# logger_thruhole_2.net
KiCad netlist of a schematic drawn in EAGLE
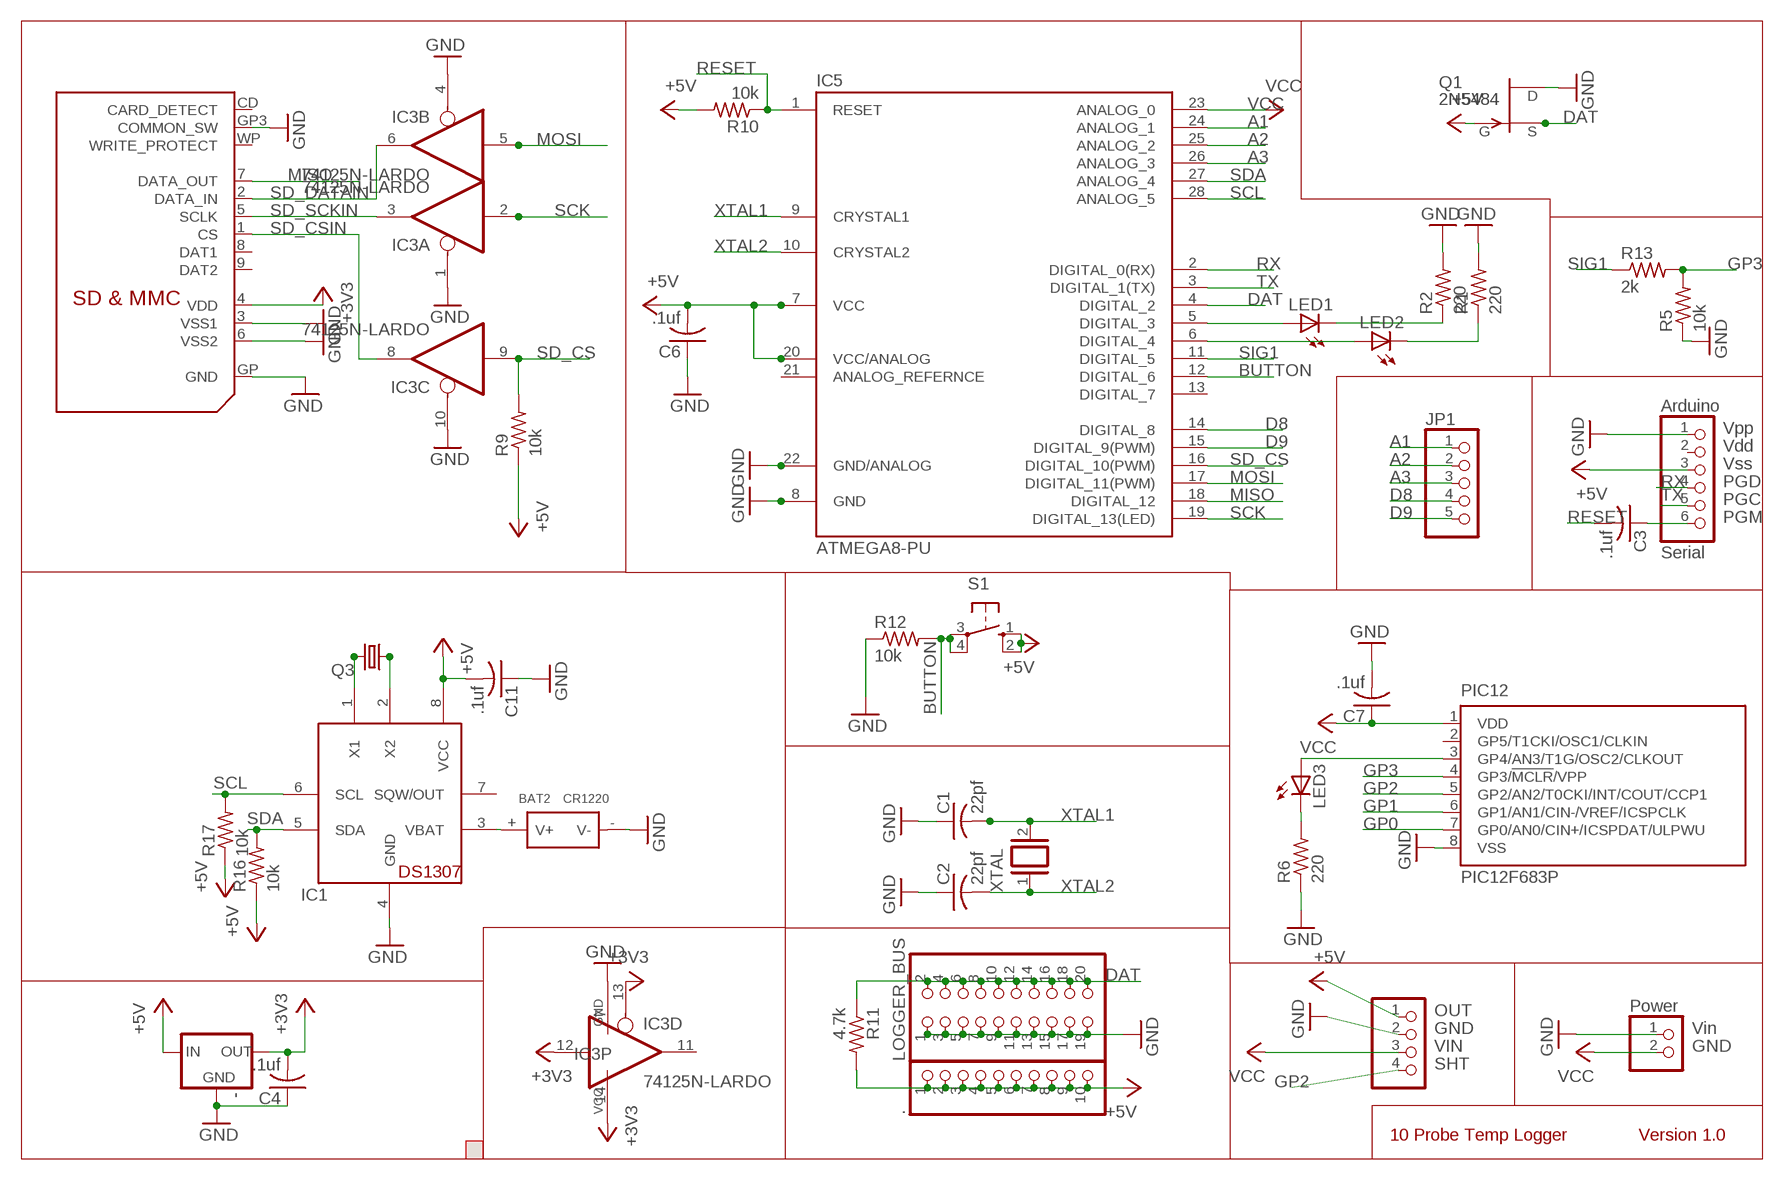
[diagram p0: schematic, sheet 1]

(export (version "E")
  (design (tool "Eeschema 10.0.6"))
  (components
    (comp (ref "'")
      (value "MCP1700TRI")
      (footprint "eagle-import:TO92")
      (libsource (lib "eagle-import") (part "MCP1700TRI"))
    )
    (comp (ref ".")
      (value "PINHD-1X10")
      (footprint "eagle-import:1X10")
      (libsource (lib "eagle-import") (part "PINHD-1X10"))
    )
    (comp (ref "BAT2")
      (value "CR1220")
      (footprint "eagle-import:BAT2P-SMD-16.4-CR1220")
      (libsource (lib "eagle-import") (part "SMD-BATTERY-CELL-HOLDER-PLASTIC"))
    )
    (comp (ref "C1")
      (value "22pf")
      (footprint "eagle-import:C025-025X050")
      (libsource (lib "eagle-import") (part "C-US025-025X050"))
    )
    (comp (ref "C2")
      (value "22pf")
      (footprint "eagle-import:C025-025X050")
      (libsource (lib "eagle-import") (part "C-US025-025X050"))
    )
    (comp (ref "C3")
      (value ".1uf")
      (footprint "eagle-import:C025-025X050")
      (libsource (lib "eagle-import") (part "C-US025-025X050"))
    )
    (comp (ref "C4")
      (value ".1uf")
      (footprint "eagle-import:C025-025X050")
      (libsource (lib "eagle-import") (part "C-US025-025X050"))
    )
    (comp (ref "C6")
      (value ".1uf")
      (footprint "eagle-import:C025-025X050")
      (libsource (lib "eagle-import") (part "C-US025-025X050"))
    )
    (comp (ref "C7")
      (value ".1uf")
      (footprint "eagle-import:C025-025X050")
      (libsource (lib "eagle-import") (part "C-US025-025X050"))
    )
    (comp (ref "C11")
      (value ".1uf")
      (footprint "eagle-import:C025-025X050")
      (libsource (lib "eagle-import") (part "C-US025-025X050"))
    )
    (comp (ref "IC1")
      (value "DS1307")
      (footprint "eagle-import:DIL08")
      (libsource (lib "eagle-import") (part "DS1307"))
    )
    (comp (ref "IC3")
      (value "74125N-LARDO")
      (footprint "eagle-import:DIL14-LARDO")
      (libsource (lib "eagle-import") (part "74125N-LARDO"))
    )
    (comp (ref "IC5")
      (value "ATMEGA8-PU")
      (footprint "eagle-import:DIL28-3")
      (libsource (lib "eagle-import") (part "ATMEGA8-PU"))
    )
    (comp (ref "JP1")
      (value "PINHD-1X5")
      (footprint "eagle-import:1X05")
      (libsource (lib "eagle-import") (part "PINHD-1X5"))
    )
    (comp (ref "JP2")
      (value "PINHD-1X6")
      (footprint "eagle-import:1X06")
      (libsource (lib "eagle-import") (part "PINHD-1X6"))
    )
    (comp (ref "LED1")
      (value "LEDLZR181")
      (footprint "eagle-import:LZR181")
      (libsource (lib "eagle-import") (part "LEDLZR181"))
    )
    (comp (ref "LED2")
      (value "LEDLZR181")
      (footprint "eagle-import:LZR181")
      (libsource (lib "eagle-import") (part "LEDLZR181"))
    )
    (comp (ref "LED3")
      (value "LEDLZR181")
      (footprint "eagle-import:LZR181")
      (libsource (lib "eagle-import") (part "LEDLZR181"))
    )
    (comp (ref "LOGGER_BUS")
      (value "PINHD-2X10")
      (footprint "eagle-import:2X10")
      (libsource (lib "eagle-import") (part "PINHD-2X10"))
    )
    (comp (ref "PIC12")
      (value "PIC12F683P")
      (footprint "eagle-import:DIL8")
      (fields (field (name "MF") "MICROCHIP") (field (name "MPN") "PIC12F683-I/P"))
      (libsource (lib "eagle-import") (part "PIC12F683P"))
    )
    (comp (ref "POWER")
      (value "PINHD-1X2")
      (footprint "eagle-import:1X02")
      (libsource (lib "eagle-import") (part "PINHD-1X2"))
    )
    (comp (ref "Q1")
      (value "2N5484")
      (footprint "eagle-import:TO92-")
      (libsource (lib "eagle-import") (part "?5482N4"))
    )
    (comp (ref "Q3")
      (value "CRYSTALTC38H")
      (footprint "eagle-import:TC38H")
      (libsource (lib "eagle-import") (part "CRYSTALTC38H"))
    )
    (comp (ref "R1")
      (value "220")
      (footprint "eagle-import:0207_2V")
      (libsource (lib "eagle-import") (part "R-US_0207/2V"))
    )
    (comp (ref "R2")
      (value "220")
      (footprint "eagle-import:0207_2V")
      (libsource (lib "eagle-import") (part "R-US_0207/2V"))
    )
    (comp (ref "R5")
      (value "10k")
      (footprint "eagle-import:0207_2V")
      (libsource (lib "eagle-import") (part "R-US_0207/2V"))
    )
    (comp (ref "R6")
      (value "220")
      (footprint "eagle-import:0207_2V")
      (libsource (lib "eagle-import") (part "R-US_0207/2V"))
    )
    (comp (ref "R9")
      (value "10k")
      (footprint "eagle-import:0207_2V")
      (libsource (lib "eagle-import") (part "R-US_0207/2V"))
    )
    (comp (ref "R10")
      (value "10k")
      (footprint "eagle-import:0207_2V")
      (libsource (lib "eagle-import") (part "R-US_0207/2V"))
    )
    (comp (ref "R11")
      (value "4.7k")
      (footprint "eagle-import:0207_2V")
      (libsource (lib "eagle-import") (part "R-US_0207/2V"))
    )
    (comp (ref "R12")
      (value "10k")
      (footprint "eagle-import:0207_2V")
      (libsource (lib "eagle-import") (part "R-US_0207/2V"))
    )
    (comp (ref "R13")
      (value "2k")
      (footprint "eagle-import:0207_2V")
      (libsource (lib "eagle-import") (part "R-US_0207/2V"))
    )
    (comp (ref "R16")
      (value "10k")
      (footprint "eagle-import:0207_2V")
      (libsource (lib "eagle-import") (part "R-US_0207/2V"))
    )
    (comp (ref "R17")
      (value "10k")
      (footprint "eagle-import:0207_2V")
      (libsource (lib "eagle-import") (part "R-US_0207/2V"))
    )
    (comp (ref "REG")
      (value "PINHD-1X4")
      (footprint "eagle-import:1X04")
      (libsource (lib "eagle-import") (part "PINHD-1X4"))
    )
    (comp (ref "S1")
      (value "10-XX")
      (footprint "eagle-import:B3F-10XX")
      (fields (field (name "MPN") "B3F-1000"))
      (libsource (lib "eagle-import") (part "10-XX"))
    )
    (comp (ref "U$2")
      (value "SDMMC06132")
      (footprint "eagle-import:06132")
      (libsource (lib "eagle-import") (part "SDMMC06132"))
    )
    (comp (ref "XTAL")
      (value "XTAL/S")
      (footprint "eagle-import:QS")
      (libsource (lib "eagle-import") (part "XTAL/S"))
    )
  )
  (nets
    (net (code "1") (name "+3V3") (class "Default")
      (node (ref "'") (pin "3") (pinfunction "OUT_3") (pintype "passive"))
      (node (ref "C4") (pin "2") (pinfunction "2_2") (pintype "passive"))
      (node (ref "IC3") (pin "12") (pinfunction "I_12") (pintype "input"))
      (node (ref "IC3") (pin "13") (pinfunction "OE_13") (pintype "input"))
      (node (ref "IC3") (pin "14") (pinfunction "VCC_14") (pintype "power_in"))
      (node (ref "U$2") (pin "4") (pinfunction "VDD_4") (pintype "power_in"))
    )
    (net (code "2") (name "+5V") (class "Default")
      (node (ref "'") (pin "2") (pinfunction "IN_2") (pintype "input"))
      (node (ref ".") (pin "1") (pinfunction "1_1") (pintype "passive"))
      (node (ref ".") (pin "10") (pinfunction "10_10") (pintype "passive"))
      (node (ref ".") (pin "2") (pinfunction "2_2") (pintype "passive"))
      (node (ref ".") (pin "3") (pinfunction "3_3") (pintype "passive"))
      (node (ref ".") (pin "4") (pinfunction "4_4") (pintype "passive"))
      (node (ref ".") (pin "5") (pinfunction "5_5") (pintype "passive"))
      (node (ref ".") (pin "6") (pinfunction "6_6") (pintype "passive"))
      (node (ref ".") (pin "7") (pinfunction "7_7") (pintype "passive"))
      (node (ref ".") (pin "8") (pinfunction "8_8") (pintype "passive"))
      (node (ref ".") (pin "9") (pinfunction "9_9") (pintype "passive"))
      (node (ref "C11") (pin "2") (pinfunction "2_2") (pintype "passive"))
      (node (ref "C6") (pin "2") (pinfunction "2_2") (pintype "passive"))
      (node (ref "IC1") (pin "8") (pinfunction "VCC_8") (pintype "power_in"))
      (node (ref "IC5") (pin "20") (pinfunction "VCC/ANALOG_20") (pintype "passive"))
      (node (ref "IC5") (pin "7") (pinfunction "VCC_7") (pintype "power_in"))
      (node (ref "JP2") (pin "3") (pinfunction "3_3") (pintype "passive"))
      (node (ref "Q1") (pin "1") (pinfunction "G_1") (pintype "passive"))
      (node (ref "R10") (pin "2") (pinfunction "2_2") (pintype "passive"))
      (node (ref "R11") (pin "2") (pinfunction "2_2") (pintype "passive"))
      (node (ref "R16") (pin "1") (pinfunction "1_1") (pintype "passive"))
      (node (ref "R17") (pin "1") (pinfunction "1_1") (pintype "passive"))
      (node (ref "R9") (pin "1") (pinfunction "1_1") (pintype "passive"))
      (node (ref "REG") (pin "1") (pinfunction "1_1") (pintype "passive"))
      (node (ref "S1") (pin "1") (pinfunction "S_1") (pintype "passive"))
      (node (ref "S1") (pin "2") (pinfunction "S1_2") (pintype "passive"))
    )
    (net (code "3") (name "/A1") (class "Default")
      (node (ref "IC5") (pin "24") (pinfunction "ANALOG_1_24") (pintype "bidirectional"))
      (node (ref "JP1") (pin "1") (pinfunction "1_1") (pintype "passive"))
    )
    (net (code "4") (name "/A2") (class "Default")
      (node (ref "IC5") (pin "25") (pinfunction "ANALOG_2_25") (pintype "bidirectional"))
      (node (ref "JP1") (pin "2") (pinfunction "2_2") (pintype "passive"))
    )
    (net (code "5") (name "/A3") (class "Default")
      (node (ref "IC5") (pin "26") (pinfunction "ANALOG_3_26") (pintype "bidirectional"))
      (node (ref "JP1") (pin "3") (pinfunction "3_3") (pintype "passive"))
    )
    (net (code "6") (name "/BUTTON") (class "Default")
      (node (ref "IC5") (pin "12") (pinfunction "DIGITAL_6_12") (pintype "bidirectional"))
      (node (ref "R12") (pin "2") (pinfunction "2_2") (pintype "passive"))
      (node (ref "S1") (pin "3") (pinfunction "P_3") (pintype "passive"))
      (node (ref "S1") (pin "4") (pinfunction "P1_4") (pintype "passive"))
    )
    (net (code "7") (name "/D8") (class "Default")
      (node (ref "IC5") (pin "14") (pinfunction "DIGITAL_8_14") (pintype "bidirectional"))
      (node (ref "JP1") (pin "4") (pinfunction "4_4") (pintype "passive"))
    )
    (net (code "8") (name "/D9") (class "Default")
      (node (ref "IC5") (pin "15") (pinfunction "DIGITAL_9(PWM)_15") (pintype "bidirectional"))
      (node (ref "JP1") (pin "5") (pinfunction "5_5") (pintype "passive"))
    )
    (net (code "9") (name "/DAT") (class "Default")
      (node (ref "IC5") (pin "4") (pinfunction "DIGITAL_2_4") (pintype "bidirectional"))
      (node (ref "LOGGER_BUS") (pin "10") (pinfunction "10_10") (pintype "passive"))
      (node (ref "LOGGER_BUS") (pin "12") (pinfunction "12_12") (pintype "passive"))
      (node (ref "LOGGER_BUS") (pin "14") (pinfunction "14_14") (pintype "passive"))
      (node (ref "LOGGER_BUS") (pin "16") (pinfunction "16_16") (pintype "passive"))
      (node (ref "LOGGER_BUS") (pin "18") (pinfunction "18_18") (pintype "passive"))
      (node (ref "LOGGER_BUS") (pin "2") (pinfunction "2_2") (pintype "passive"))
      (node (ref "LOGGER_BUS") (pin "20") (pinfunction "20_20") (pintype "passive"))
      (node (ref "LOGGER_BUS") (pin "4") (pinfunction "4_4") (pintype "passive"))
      (node (ref "LOGGER_BUS") (pin "6") (pinfunction "6_6") (pintype "passive"))
      (node (ref "LOGGER_BUS") (pin "8") (pinfunction "8_8") (pintype "passive"))
      (node (ref "Q1") (pin "2") (pinfunction "S_2") (pintype "passive"))
      (node (ref "R11") (pin "1") (pinfunction "1_1") (pintype "passive"))
    )
    (net (code "10") (name "/GP0") (class "Default")
      (node (ref "PIC12") (pin "7") (pinfunction "GP0/AN0/CIN+/ICSPDAT/ULPWU_7") (pintype "bidirectional"))
    )
    (net (code "11") (name "/GP1") (class "Default")
      (node (ref "PIC12") (pin "6") (pinfunction "GP1/AN1/CIN-/VREF/ICSPCLK_6") (pintype "bidirectional"))
    )
    (net (code "12") (name "/GP2") (class "Default")
      (node (ref "PIC12") (pin "5") (pinfunction "GP2/AN2/T0CKI/INT/COUT/CCP1_5") (pintype "bidirectional"))
      (node (ref "REG") (pin "4") (pinfunction "4_4") (pintype "passive"))
    )
    (net (code "13") (name "/GP3") (class "Default")
      (node (ref "PIC12") (pin "4") (pinfunction "GP3/~{MCLR}/VPP_4") (pintype "bidirectional"))
      (node (ref "R13") (pin "2") (pinfunction "2_2") (pintype "passive"))
      (node (ref "R5") (pin "2") (pinfunction "2_2") (pintype "passive"))
    )
    (net (code "14") (name "/MISO") (class "Default")
      (node (ref "IC5") (pin "18") (pinfunction "DIGITAL_12_18") (pintype "bidirectional"))
      (node (ref "U$2") (pin "7") (pinfunction "DATA_OUT_7") (pintype "output"))
    )
    (net (code "15") (name "/MOSI") (class "Default")
      (node (ref "IC3") (pin "5") (pinfunction "I_5") (pintype "input"))
      (node (ref "IC5") (pin "17") (pinfunction "DIGITAL_11(PWM)_17") (pintype "bidirectional"))
    )
    (net (code "16") (name "/RESET") (class "Default")
      (node (ref "C3") (pin "2") (pinfunction "2_2") (pintype "passive"))
      (node (ref "IC5") (pin "1") (pinfunction "RESET_1") (pintype "bidirectional"))
      (node (ref "R10") (pin "1") (pinfunction "1_1") (pintype "passive"))
    )
    (net (code "17") (name "/RX") (class "Default")
      (node (ref "IC5") (pin "2") (pinfunction "DIGITAL_0(RX)_2") (pintype "bidirectional"))
      (node (ref "JP2") (pin "4") (pinfunction "4_4") (pintype "passive"))
    )
    (net (code "18") (name "/SCK") (class "Default")
      (node (ref "IC3") (pin "2") (pinfunction "I_2") (pintype "input"))
      (node (ref "IC5") (pin "19") (pinfunction "DIGITAL_13(LED)_19") (pintype "bidirectional"))
    )
    (net (code "19") (name "/SCL") (class "Default")
      (node (ref "IC1") (pin "6") (pinfunction "SCL_6") (pintype "bidirectional"))
      (node (ref "IC5") (pin "28") (pinfunction "ANALOG_5_28") (pintype "bidirectional"))
      (node (ref "R17") (pin "2") (pinfunction "2_2") (pintype "passive"))
    )
    (net (code "20") (name "/SDA") (class "Default")
      (node (ref "IC1") (pin "5") (pinfunction "SDA_5") (pintype "bidirectional"))
      (node (ref "IC5") (pin "27") (pinfunction "ANALOG_4_27") (pintype "bidirectional"))
      (node (ref "R16") (pin "2") (pinfunction "2_2") (pintype "passive"))
    )
    (net (code "21") (name "/SD_CS") (class "Default")
      (node (ref "IC3") (pin "9") (pinfunction "I_9") (pintype "input"))
      (node (ref "IC5") (pin "16") (pinfunction "DIGITAL_10(PWM)_16") (pintype "bidirectional"))
      (node (ref "R9") (pin "2") (pinfunction "2_2") (pintype "passive"))
    )
    (net (code "22") (name "/SD_CSIN") (class "Default")
      (node (ref "IC3") (pin "8") (pinfunction "O_8") (pintype "tri_state"))
      (node (ref "U$2") (pin "1") (pinfunction "CS_1") (pintype "input"))
    )
    (net (code "23") (name "/SD_DATAIN") (class "Default")
      (node (ref "IC3") (pin "6") (pinfunction "O_6") (pintype "tri_state"))
      (node (ref "U$2") (pin "2") (pinfunction "DATA_IN_2") (pintype "input"))
    )
    (net (code "24") (name "/SD_SCKIN") (class "Default")
      (node (ref "IC3") (pin "3") (pinfunction "O_3") (pintype "tri_state"))
      (node (ref "U$2") (pin "5") (pinfunction "SCLK_5") (pintype "input"))
    )
    (net (code "25") (name "/SIG1") (class "Default")
      (node (ref "IC5") (pin "11") (pinfunction "DIGITAL_5_11") (pintype "bidirectional"))
      (node (ref "R13") (pin "1") (pinfunction "1_1") (pintype "passive"))
    )
    (net (code "26") (name "/TX") (class "Default")
      (node (ref "IC5") (pin "3") (pinfunction "DIGITAL_1(TX)_3") (pintype "bidirectional"))
      (node (ref "JP2") (pin "5") (pinfunction "5_5") (pintype "passive"))
    )
    (net (code "27") (name "/XTAL1") (class "Default")
      (node (ref "C1") (pin "2") (pinfunction "2_2") (pintype "passive"))
      (node (ref "IC5") (pin "9") (pinfunction "CRYSTAL1_9") (pintype "bidirectional"))
      (node (ref "XTAL") (pin "2") (pinfunction "2_2") (pintype "passive"))
    )
    (net (code "28") (name "/XTAL2") (class "Default")
      (node (ref "C2") (pin "2") (pinfunction "2_2") (pintype "passive"))
      (node (ref "IC5") (pin "10") (pinfunction "CRYSTAL2_10") (pintype "bidirectional"))
      (node (ref "XTAL") (pin "1") (pinfunction "1_1") (pintype "passive"))
    )
    (net (code "29") (name "GND") (class "Default")
      (node (ref "'") (pin "1") (pinfunction "GND_1") (pintype "input"))
      (node (ref "BAT2") (pin "-") (pinfunction "V-_-") (pintype "bidirectional"))
      (node (ref "C1") (pin "1") (pinfunction "1_1") (pintype "passive"))
      (node (ref "C11") (pin "1") (pinfunction "1_1") (pintype "passive"))
      (node (ref "C2") (pin "1") (pinfunction "1_1") (pintype "passive"))
      (node (ref "C4") (pin "1") (pinfunction "1_1") (pintype "passive"))
      (node (ref "C6") (pin "1") (pinfunction "1_1") (pintype "passive"))
      (node (ref "C7") (pin "2") (pinfunction "2_2") (pintype "passive"))
      (node (ref "IC1") (pin "4") (pinfunction "GND_4") (pintype "power_in"))
      (node (ref "IC3") (pin "1") (pinfunction "OE_1") (pintype "input"))
      (node (ref "IC3") (pin "10") (pinfunction "OE_10") (pintype "input"))
      (node (ref "IC3") (pin "4") (pinfunction "OE_4") (pintype "input"))
      (node (ref "IC3") (pin "7") (pinfunction "GND_7") (pintype "power_in"))
      (node (ref "IC5") (pin "22") (pinfunction "GND/ANALOG_22") (pintype "power_in"))
      (node (ref "IC5") (pin "8") (pinfunction "GND_8") (pintype "power_in"))
      (node (ref "JP2") (pin "1") (pinfunction "1_1") (pintype "passive"))
      (node (ref "LOGGER_BUS") (pin "1") (pinfunction "1_1") (pintype "passive"))
      (node (ref "LOGGER_BUS") (pin "11") (pinfunction "11_11") (pintype "passive"))
      (node (ref "LOGGER_BUS") (pin "13") (pinfunction "13_13") (pintype "passive"))
      (node (ref "LOGGER_BUS") (pin "15") (pinfunction "15_15") (pintype "passive"))
      (node (ref "LOGGER_BUS") (pin "17") (pinfunction "17_17") (pintype "passive"))
      (node (ref "LOGGER_BUS") (pin "19") (pinfunction "19_19") (pintype "passive"))
      (node (ref "LOGGER_BUS") (pin "3") (pinfunction "3_3") (pintype "passive"))
      (node (ref "LOGGER_BUS") (pin "5") (pinfunction "5_5") (pintype "passive"))
      (node (ref "LOGGER_BUS") (pin "7") (pinfunction "7_7") (pintype "passive"))
      (node (ref "LOGGER_BUS") (pin "9") (pinfunction "9_9") (pintype "passive"))
      (node (ref "PIC12") (pin "8") (pinfunction "VSS_8") (pintype "power_in"))
      (node (ref "POWER") (pin "1") (pinfunction "1_1") (pintype "passive"))
      (node (ref "Q1") (pin "3") (pinfunction "D_3") (pintype "passive"))
      (node (ref "R1") (pin "2") (pinfunction "2_2") (pintype "passive"))
      (node (ref "R12") (pin "1") (pinfunction "1_1") (pintype "passive"))
      (node (ref "R2") (pin "2") (pinfunction "2_2") (pintype "passive"))
      (node (ref "R5") (pin "1") (pinfunction "1_1") (pintype "passive"))
      (node (ref "R6") (pin "1") (pinfunction "1_1") (pintype "passive"))
      (node (ref "REG") (pin "2") (pinfunction "2_2") (pintype "passive"))
      (node (ref "U$2") (pin "3") (pinfunction "VSS1_3") (pintype "power_in"))
      (node (ref "U$2") (pin "6") (pinfunction "VSS2_6") (pintype "power_in"))
      (node (ref "U$2") (pin "GP") (pinfunction "GND_GP") (pintype "power_in"))
      (node (ref "U$2") (pin "GP3") (pinfunction "COMMON_SW_GP3") (pintype "passive"))
    )
    (net (code "30") (name "Net-(BAT2-V+)") (class "Default")
      (node (ref "BAT2") (pin "+") (pinfunction "V+_+") (pintype "bidirectional"))
      (node (ref "IC1") (pin "3") (pinfunction "VBAT_3") (pintype "power_in"))
    )
    (net (code "31") (name "Net-(C3-Pad1)") (class "Default")
      (node (ref "C3") (pin "1") (pinfunction "1_1") (pintype "passive"))
      (node (ref "JP2") (pin "6") (pinfunction "6_6") (pintype "passive"))
    )
    (net (code "32") (name "Net-(IC1-X1)") (class "Default")
      (node (ref "IC1") (pin "1") (pinfunction "X1_1") (pintype "passive"))
      (node (ref "Q3") (pin "2") (pinfunction "2_2") (pintype "passive"))
    )
    (net (code "33") (name "Net-(IC1-X2)") (class "Default")
      (node (ref "IC1") (pin "2") (pinfunction "X2_2") (pintype "passive"))
      (node (ref "Q3") (pin "1") (pinfunction "1_1") (pintype "passive"))
    )
    (net (code "34") (name "Net-(IC5-DIGITAL_3)") (class "Default")
      (node (ref "IC5") (pin "5") (pinfunction "DIGITAL_3_5") (pintype "bidirectional"))
      (node (ref "LED1") (pin "A") (pinfunction "A_A") (pintype "passive"))
    )
    (net (code "35") (name "Net-(IC5-DIGITAL_4)") (class "Default")
      (node (ref "IC5") (pin "6") (pinfunction "DIGITAL_4_6") (pintype "bidirectional"))
      (node (ref "LED2") (pin "A") (pinfunction "A_A") (pintype "passive"))
    )
    (net (code "36") (name "Net-(LED1-C)") (class "Default")
      (node (ref "LED1") (pin "K") (pinfunction "C_K") (pintype "passive"))
      (node (ref "R2") (pin "1") (pinfunction "1_1") (pintype "passive"))
    )
    (net (code "37") (name "Net-(LED2-C)") (class "Default")
      (node (ref "LED2") (pin "K") (pinfunction "C_K") (pintype "passive"))
      (node (ref "R1") (pin "1") (pinfunction "1_1") (pintype "passive"))
    )
    (net (code "38") (name "Net-(LED3-C)") (class "Default")
      (node (ref "LED3") (pin "K") (pinfunction "C_K") (pintype "passive"))
      (node (ref "R6") (pin "2") (pinfunction "2_2") (pintype "passive"))
    )
    (net (code "39") (name "Net-(PIC12-GP4{slash}AN3{slash}T1G{slash}OSC2{slash}CLKOUT)") (class "Default")
      (node (ref "LED3") (pin "A") (pinfunction "A_A") (pintype "passive"))
      (node (ref "PIC12") (pin "3") (pinfunction "GP4/AN3/T1G/OSC2/CLKOUT_3") (pintype "bidirectional"))
    )
    (net (code "40") (name "VCC") (class "Default")
      (node (ref "C7") (pin "1") (pinfunction "1_1") (pintype "passive"))
      (node (ref "IC5") (pin "23") (pinfunction "ANALOG_0_23") (pintype "bidirectional"))
      (node (ref "PIC12") (pin "1") (pinfunction "VDD_1") (pintype "power_in"))
      (node (ref "POWER") (pin "2") (pinfunction "2_2") (pintype "passive"))
      (node (ref "REG") (pin "3") (pinfunction "3_3") (pintype "passive"))
    )
    (net (code "41") (name "unconnected-(IC1-SQW{slash}OUT-Pad7)") (class "Default")
      (node (ref "IC1") (pin "7") (pinfunction "SQW/OUT_7") (pintype "bidirectional"))
    )
    (net (code "42") (name "unconnected-(IC3D-O-Pad11)") (class "Default")
      (node (ref "IC3") (pin "11") (pinfunction "O_11") (pintype "tri_state"))
    )
    (net (code "43") (name "unconnected-(IC5-ANALOG_REFERNCE-Pad21)") (class "Default")
      (node (ref "IC5") (pin "21") (pinfunction "ANALOG_REFERNCE_21") (pintype "passive"))
    )
    (net (code "44") (name "unconnected-(IC5-DIGITAL_7-Pad13)") (class "Default")
      (node (ref "IC5") (pin "13") (pinfunction "DIGITAL_7_13") (pintype "bidirectional"))
    )
    (net (code "45") (name "unconnected-(JP2-Pad2)") (class "Default")
      (node (ref "JP2") (pin "2") (pinfunction "2_2") (pintype "passive"))
    )
    (net (code "46") (name "unconnected-(PIC12-GP5{slash}T1CKI{slash}OSC1{slash}CLKIN-Pad2)") (class "Default")
      (node (ref "PIC12") (pin "2") (pinfunction "GP5/T1CKI/OSC1/CLKIN_2") (pintype "bidirectional"))
    )
    (net (code "47") (name "unconnected-(U$2-CARD_DETECT-PadCD)") (class "Default")
      (node (ref "U$2") (pin "CD") (pinfunction "CARD_DETECT_CD") (pintype "passive"))
    )
    (net (code "48") (name "unconnected-(U$2-DAT1-Pad8)") (class "Default")
      (node (ref "U$2") (pin "8") (pinfunction "DAT1_8") (pintype "bidirectional"))
    )
    (net (code "49") (name "unconnected-(U$2-DAT2-Pad9)") (class "Default")
      (node (ref "U$2") (pin "9") (pinfunction "DAT2_9") (pintype "bidirectional"))
    )
    (net (code "50") (name "unconnected-(U$2-WRITE_PROTECT-PadWP)") (class "Default")
      (node (ref "U$2") (pin "WP") (pinfunction "WRITE_PROTECT_WP") (pintype "passive"))
    )
  )
)
